# HHV_SCA_Demo-P1.net
KiCad netlist of a schematic drawn in EAGLE
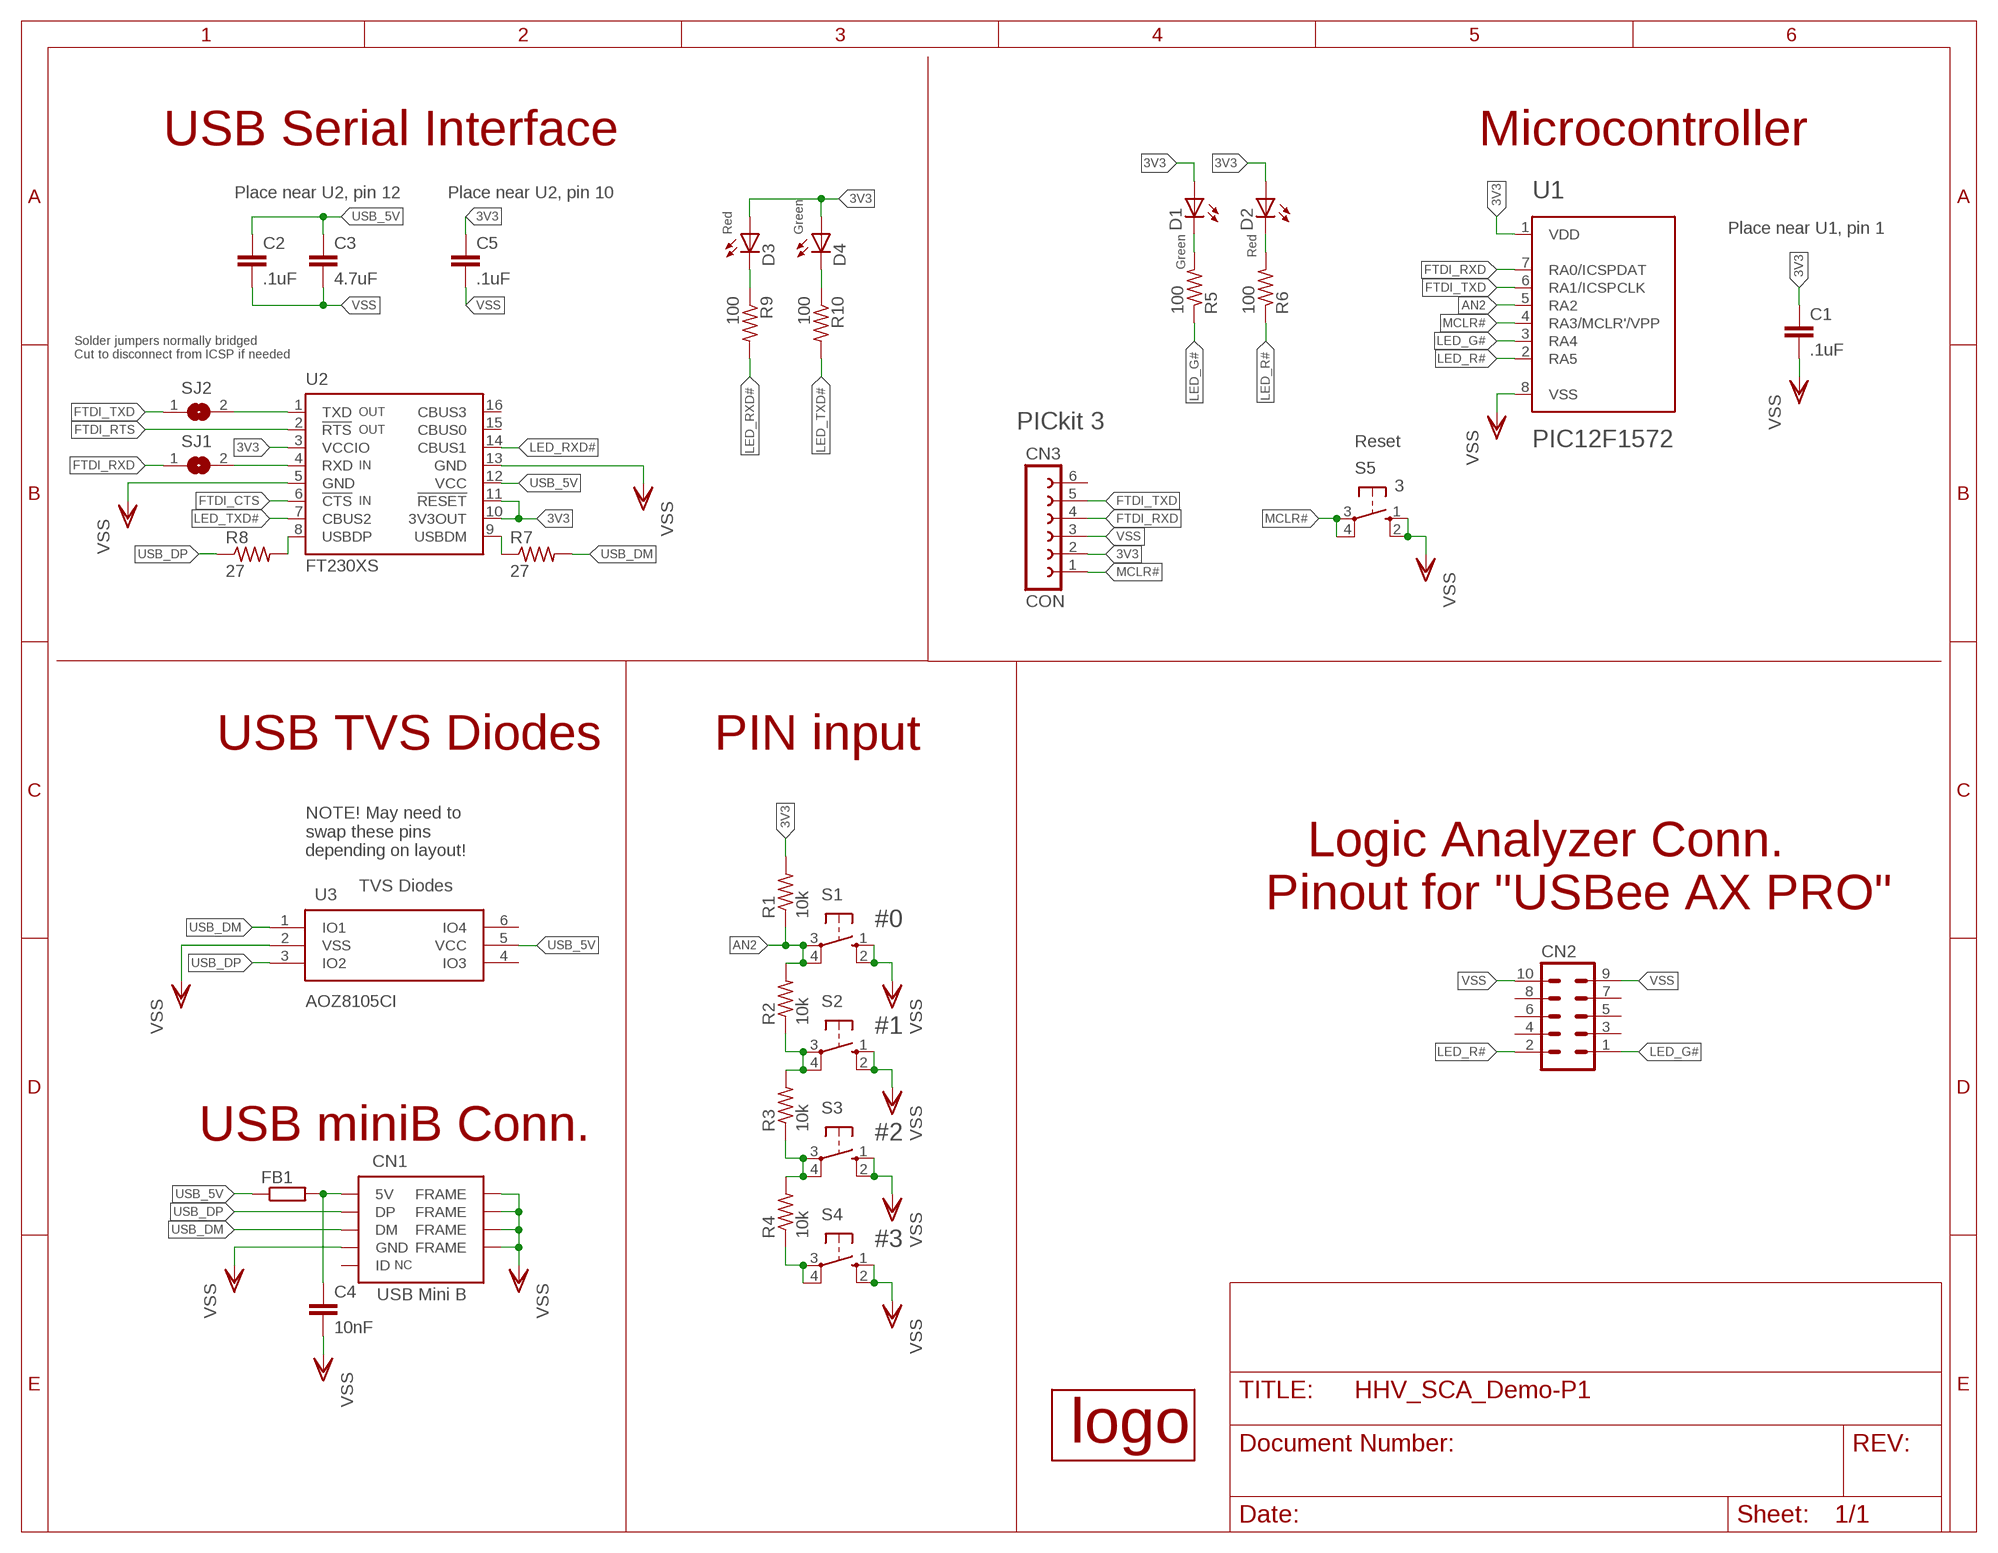
[diagram p0: schematic, sheet 1]

(export (version "E")
  (design (tool "Eeschema 10.0.6"))
  (components
    (comp (ref "C1")
      (value ".1uF")
      (footprint "eagle-import:C0603K")
      (libsource (lib "eagle-import") (part "C-EUC0603K"))
    )
    (comp (ref "C2")
      (value ".1uF")
      (footprint "eagle-import:C0603K")
      (libsource (lib "eagle-import") (part "C-EUC0603K"))
    )
    (comp (ref "C3")
      (value "4.7uF")
      (footprint "eagle-import:C0603K")
      (libsource (lib "eagle-import") (part "C-EUC0603K"))
    )
    (comp (ref "C4")
      (value "10nF")
      (footprint "eagle-import:C0603K")
      (libsource (lib "eagle-import") (part "C-EUC0603K"))
    )
    (comp (ref "C5")
      (value ".1uF")
      (footprint "eagle-import:C0603K")
      (libsource (lib "eagle-import") (part "C-EUC0603K"))
    )
    (comp (ref "CN1")
      (value "MINIUSB-SMD")
      (footprint "eagle-import:MINIUSB-SMD")
      (libsource (lib "eagle-import") (part "MINIUSB-SMD"))
    )
    (comp (ref "CN2")
      (value "MA05-2")
      (footprint "eagle-import:MA05-2")
      (libsource (lib "eagle-import") (part "MA05-2"))
    )
    (comp (ref "CN3")
      (value "CON")
      (footprint "eagle-import:FE06")
      (libsource (lib "eagle-import") (part "FE06-1"))
    )
    (comp (ref "D1")
      (value "LED3MM")
      (footprint "eagle-import:LED3MM")
      (libsource (lib "eagle-import") (part "LED3MM"))
    )
    (comp (ref "D2")
      (value "LED3MM")
      (footprint "eagle-import:LED3MM")
      (libsource (lib "eagle-import") (part "LED3MM"))
    )
    (comp (ref "D3")
      (value "LED3MM")
      (footprint "eagle-import:LED3MM")
      (libsource (lib "eagle-import") (part "LED3MM"))
    )
    (comp (ref "D4")
      (value "LED3MM")
      (footprint "eagle-import:LED3MM")
      (libsource (lib "eagle-import") (part "LED3MM"))
    )
    (comp (ref "FB1")
      (value "R-EU_R0603")
      (footprint "eagle-import:R0603")
      (libsource (lib "eagle-import") (part "R-EU_R0603"))
    )
    (comp (ref "R1")
      (value "10k")
      (footprint "eagle-import:R0603")
      (libsource (lib "eagle-import") (part "R-US_R0603"))
    )
    (comp (ref "R2")
      (value "10k")
      (footprint "eagle-import:R0603")
      (libsource (lib "eagle-import") (part "R-US_R0603"))
    )
    (comp (ref "R3")
      (value "10k")
      (footprint "eagle-import:R0603")
      (libsource (lib "eagle-import") (part "R-US_R0603"))
    )
    (comp (ref "R4")
      (value "10k")
      (footprint "eagle-import:R0603")
      (libsource (lib "eagle-import") (part "R-US_R0603"))
    )
    (comp (ref "R5")
      (value "100")
      (footprint "eagle-import:R0603")
      (libsource (lib "eagle-import") (part "R-US_R0603"))
    )
    (comp (ref "R6")
      (value "100")
      (footprint "eagle-import:R0603")
      (libsource (lib "eagle-import") (part "R-US_R0603"))
    )
    (comp (ref "R7")
      (value "27")
      (footprint "eagle-import:R0402")
      (libsource (lib "eagle-import") (part "R-US_R0402"))
    )
    (comp (ref "R8")
      (value "27")
      (footprint "eagle-import:R0402")
      (libsource (lib "eagle-import") (part "R-US_R0402"))
    )
    (comp (ref "R9")
      (value "100")
      (footprint "eagle-import:R0603")
      (libsource (lib "eagle-import") (part "R-US_R0603"))
    )
    (comp (ref "R10")
      (value "100")
      (footprint "eagle-import:R0603")
      (libsource (lib "eagle-import") (part "R-US_R0603"))
    )
    (comp (ref "S1")
      (value "10-XX")
      (footprint "eagle-import:B3F-10XX")
      (fields (field (name "MPN") "B3F-1000"))
      (libsource (lib "eagle-import") (part "10-XX"))
    )
    (comp (ref "S2")
      (value "10-XX")
      (footprint "eagle-import:B3F-10XX")
      (fields (field (name "MPN") "B3F-1000"))
      (libsource (lib "eagle-import") (part "10-XX"))
    )
    (comp (ref "S3")
      (value "10-XX")
      (footprint "eagle-import:B3F-10XX")
      (fields (field (name "MPN") "B3F-1000"))
      (libsource (lib "eagle-import") (part "10-XX"))
    )
    (comp (ref "S4")
      (value "10-XX")
      (footprint "eagle-import:B3F-10XX")
      (fields (field (name "MPN") "B3F-1000"))
      (libsource (lib "eagle-import") (part "10-XX"))
    )
    (comp (ref "S5")
      (value "3")
      (footprint "eagle-import:B3F-10XX")
      (fields (field (name "MPN") "B3F-1000"))
      (libsource (lib "eagle-import") (part "10-XX"))
    )
    (comp (ref "SJ1") (value "SJ") (footprint "eagle-import:SJ") (libsource (lib "eagle-import") (part "SJ")))
    (comp (ref "SJ2") (value "SJ") (footprint "eagle-import:SJ") (libsource (lib "eagle-import") (part "SJ")))
    (comp (ref "U$1")
      (value "KBELOGO-SILK")
      (footprint "eagle-import:KBELOGO-SILK")
      (libsource (lib "eagle-import") (part "KBELOGO-SILK"))
    )
    (comp (ref "U1")
      (value "PIC12F1572")
      (footprint "eagle-import:DIL8")
      (libsource (lib "eagle-import") (part "PIC12F1571"))
    )
    (comp (ref "U2")
      (value "FT230XS")
      (footprint "eagle-import:SSOP16")
      (libsource (lib "eagle-import") (part "FT230XS"))
    )
    (comp (ref "U3")
      (value "AOZ8105CI")
      (footprint "eagle-import:SOT23-6L")
      (libsource (lib "eagle-import") (part "AOZ8105CI"))
    )
  )
  (nets
    (net (code "1") (name "3V3") (class "Default")
      (node (ref "C1") (pin "1") (pinfunction "1_1") (pintype "passive"))
      (node (ref "C5") (pin "1") (pinfunction "1_1") (pintype "passive"))
      (node (ref "CN3") (pin "2") (pinfunction "2_2") (pintype "passive"))
      (node (ref "D1") (pin "A") (pinfunction "A_A") (pintype "passive"))
      (node (ref "D2") (pin "A") (pinfunction "A_A") (pintype "passive"))
      (node (ref "D3") (pin "A") (pinfunction "A_A") (pintype "passive"))
      (node (ref "D4") (pin "A") (pinfunction "A_A") (pintype "passive"))
      (node (ref "R1") (pin "2") (pinfunction "2_2") (pintype "passive"))
      (node (ref "U1") (pin "1") (pinfunction "VDD_1") (pintype "power_in"))
      (node (ref "U2") (pin "10") (pinfunction "3V3OUT_10") (pintype "output"))
      (node (ref "U2") (pin "11") (pinfunction "~{RESET}_11") (pintype "input"))
      (node (ref "U2") (pin "3") (pinfunction "VCCIO_3") (pintype "power_in"))
    )
    (net (code "2") (name "AN2") (class "Default")
      (node (ref "R1") (pin "1") (pinfunction "1_1") (pintype "passive"))
      (node (ref "R2") (pin "2") (pinfunction "2_2") (pintype "passive"))
      (node (ref "S1") (pin "3") (pinfunction "P_3") (pintype "passive"))
      (node (ref "S1") (pin "4") (pinfunction "P1_4") (pintype "passive"))
      (node (ref "U1") (pin "5") (pinfunction "RA2_5") (pintype "bidirectional"))
    )
    (net (code "3") (name "FTDI_CTS") (class "Default")
      (node (ref "U2") (pin "6") (pinfunction "~{CTS}_6") (pintype "input"))
    )
    (net (code "4") (name "FTDI_RTS") (class "Default")
      (node (ref "U2") (pin "2") (pinfunction "~{RTS}_2") (pintype "output"))
    )
    (net (code "5") (name "FTDI_RXD") (class "Default")
      (node (ref "CN3") (pin "4") (pinfunction "4_4") (pintype "passive"))
      (node (ref "SJ1") (pin "1") (pinfunction "1_1") (pintype "passive"))
      (node (ref "U1") (pin "7") (pinfunction "RA0/ICSPDAT_7") (pintype "bidirectional"))
    )
    (net (code "6") (name "FTDI_TXD") (class "Default")
      (node (ref "CN3") (pin "5") (pinfunction "5_5") (pintype "passive"))
      (node (ref "SJ2") (pin "1") (pinfunction "1_1") (pintype "passive"))
      (node (ref "U1") (pin "6") (pinfunction "RA1/ICSPCLK_6") (pintype "bidirectional"))
    )
    (net (code "7") (name "LED_G#") (class "Default")
      (node (ref "CN2") (pin "1") (pinfunction "1_1") (pintype "passive"))
      (node (ref "R5") (pin "1") (pinfunction "1_1") (pintype "passive"))
      (node (ref "U1") (pin "3") (pinfunction "RA4_3") (pintype "bidirectional"))
    )
    (net (code "8") (name "LED_R#") (class "Default")
      (node (ref "CN2") (pin "2") (pinfunction "2_2") (pintype "passive"))
      (node (ref "R6") (pin "1") (pinfunction "1_1") (pintype "passive"))
      (node (ref "U1") (pin "2") (pinfunction "RA5_2") (pintype "bidirectional"))
    )
    (net (code "9") (name "LED_RXD#") (class "Default")
      (node (ref "R9") (pin "2") (pinfunction "2_2") (pintype "passive"))
      (node (ref "U2") (pin "14") (pinfunction "CBUS1_14") (pintype "bidirectional"))
    )
    (net (code "10") (name "LED_TXD#") (class "Default")
      (node (ref "R10") (pin "2") (pinfunction "2_2") (pintype "passive"))
      (node (ref "U2") (pin "7") (pinfunction "CBUS2_7") (pintype "bidirectional"))
    )
    (net (code "11") (name "MCLR#") (class "Default")
      (node (ref "CN3") (pin "1") (pinfunction "1_1") (pintype "passive"))
      (node (ref "S5") (pin "3") (pinfunction "P_3") (pintype "passive"))
      (node (ref "S5") (pin "4") (pinfunction "P1_4") (pintype "passive"))
      (node (ref "U1") (pin "4") (pinfunction "RA3/MCLR'/VPP_4") (pintype "bidirectional"))
    )
    (net (code "12") (name "Net-(C4-Pad1)") (class "Default")
      (node (ref "C4") (pin "1") (pinfunction "1_1") (pintype "passive"))
      (node (ref "CN1") (pin "5V") (pinfunction "5V_5V") (pintype "bidirectional"))
      (node (ref "FB1") (pin "2") (pinfunction "2_2") (pintype "passive"))
    )
    (net (code "13") (name "Net-(D1-C)") (class "Default")
      (node (ref "D1") (pin "K") (pinfunction "C_K") (pintype "passive"))
      (node (ref "R5") (pin "2") (pinfunction "2_2") (pintype "passive"))
    )
    (net (code "14") (name "Net-(D2-C)") (class "Default")
      (node (ref "D2") (pin "K") (pinfunction "C_K") (pintype "passive"))
      (node (ref "R6") (pin "2") (pinfunction "2_2") (pintype "passive"))
    )
    (net (code "15") (name "Net-(D3-C)") (class "Default")
      (node (ref "D3") (pin "K") (pinfunction "C_K") (pintype "passive"))
      (node (ref "R9") (pin "1") (pinfunction "1_1") (pintype "passive"))
    )
    (net (code "16") (name "Net-(D4-C)") (class "Default")
      (node (ref "D4") (pin "K") (pinfunction "C_K") (pintype "passive"))
      (node (ref "R10") (pin "1") (pinfunction "1_1") (pintype "passive"))
    )
    (net (code "17") (name "Net-(S2-P)") (class "Default")
      (node (ref "R2") (pin "1") (pinfunction "1_1") (pintype "passive"))
      (node (ref "R3") (pin "2") (pinfunction "2_2") (pintype "passive"))
      (node (ref "S2") (pin "3") (pinfunction "P_3") (pintype "passive"))
      (node (ref "S2") (pin "4") (pinfunction "P1_4") (pintype "passive"))
    )
    (net (code "18") (name "Net-(S3-P)") (class "Default")
      (node (ref "R3") (pin "1") (pinfunction "1_1") (pintype "passive"))
      (node (ref "R4") (pin "2") (pinfunction "2_2") (pintype "passive"))
      (node (ref "S3") (pin "3") (pinfunction "P_3") (pintype "passive"))
      (node (ref "S3") (pin "4") (pinfunction "P1_4") (pintype "passive"))
    )
    (net (code "19") (name "Net-(S4-P)") (class "Default")
      (node (ref "R4") (pin "1") (pinfunction "1_1") (pintype "passive"))
      (node (ref "S4") (pin "3") (pinfunction "P_3") (pintype "passive"))
      (node (ref "S4") (pin "4") (pinfunction "P1_4") (pintype "passive"))
    )
    (net (code "20") (name "Net-(U2-RXD)") (class "Default")
      (node (ref "SJ1") (pin "2") (pinfunction "2_2") (pintype "passive"))
      (node (ref "U2") (pin "4") (pinfunction "RXD_4") (pintype "input"))
    )
    (net (code "21") (name "Net-(U2-TXD)") (class "Default")
      (node (ref "SJ2") (pin "2") (pinfunction "2_2") (pintype "passive"))
      (node (ref "U2") (pin "1") (pinfunction "TXD_1") (pintype "output"))
    )
    (net (code "22") (name "Net-(U2-USBDM)") (class "Default")
      (node (ref "R7") (pin "1") (pinfunction "1_1") (pintype "passive"))
      (node (ref "U2") (pin "9") (pinfunction "USBDM_9") (pintype "input"))
    )
    (net (code "23") (name "Net-(U2-USBDP)") (class "Default")
      (node (ref "R8") (pin "2") (pinfunction "2_2") (pintype "passive"))
      (node (ref "U2") (pin "8") (pinfunction "USBDP_8") (pintype "input"))
    )
    (net (code "24") (name "USB_5V") (class "Default")
      (node (ref "C2") (pin "1") (pinfunction "1_1") (pintype "passive"))
      (node (ref "C3") (pin "1") (pinfunction "1_1") (pintype "passive"))
      (node (ref "FB1") (pin "1") (pinfunction "1_1") (pintype "passive"))
      (node (ref "U2") (pin "12") (pinfunction "VCC_12") (pintype "power_in"))
      (node (ref "U3") (pin "5") (pinfunction "VCC_5") (pintype "bidirectional"))
    )
    (net (code "25") (name "USB_DM") (class "Default")
      (node (ref "CN1") (pin "USB_DM") (pinfunction "DM_USB_DM") (pintype "bidirectional"))
      (node (ref "R7") (pin "2") (pinfunction "2_2") (pintype "passive"))
      (node (ref "U3") (pin "1") (pinfunction "IO1_1") (pintype "bidirectional"))
    )
    (net (code "26") (name "USB_DP") (class "Default")
      (node (ref "CN1") (pin "USB_DP") (pinfunction "DP_USB_DP") (pintype "bidirectional"))
      (node (ref "R8") (pin "1") (pinfunction "1_1") (pintype "passive"))
      (node (ref "U3") (pin "3") (pinfunction "IO2_3") (pintype "bidirectional"))
    )
    (net (code "27") (name "VSS") (class "Default")
      (node (ref "C1") (pin "2") (pinfunction "2_2") (pintype "passive"))
      (node (ref "C2") (pin "2") (pinfunction "2_2") (pintype "passive"))
      (node (ref "C3") (pin "2") (pinfunction "2_2") (pintype "passive"))
      (node (ref "C4") (pin "2") (pinfunction "2_2") (pintype "passive"))
      (node (ref "C5") (pin "2") (pinfunction "2_2") (pintype "passive"))
      (node (ref "CN1") (pin "GND@0") (pinfunction "FRAME_GND@0") (pintype "bidirectional"))
      (node (ref "CN1") (pin "GND@1") (pinfunction "FRAME_GND@1") (pintype "bidirectional"))
      (node (ref "CN1") (pin "GND@2") (pinfunction "FRAME_GND@2") (pintype "bidirectional"))
      (node (ref "CN1") (pin "GND@3") (pinfunction "FRAME_GND@3") (pintype "bidirectional"))
      (node (ref "CN1") (pin "VSS") (pinfunction "GND_VSS") (pintype "bidirectional"))
      (node (ref "CN2") (pin "10") (pinfunction "10_10") (pintype "passive"))
      (node (ref "CN2") (pin "9") (pinfunction "9_9") (pintype "passive"))
      (node (ref "CN3") (pin "3") (pinfunction "3_3") (pintype "passive"))
      (node (ref "S1") (pin "1") (pinfunction "S_1") (pintype "passive"))
      (node (ref "S1") (pin "2") (pinfunction "S1_2") (pintype "passive"))
      (node (ref "S2") (pin "1") (pinfunction "S_1") (pintype "passive"))
      (node (ref "S2") (pin "2") (pinfunction "S1_2") (pintype "passive"))
      (node (ref "S3") (pin "1") (pinfunction "S_1") (pintype "passive"))
      (node (ref "S3") (pin "2") (pinfunction "S1_2") (pintype "passive"))
      (node (ref "S4") (pin "1") (pinfunction "S_1") (pintype "passive"))
      (node (ref "S4") (pin "2") (pinfunction "S1_2") (pintype "passive"))
      (node (ref "S5") (pin "1") (pinfunction "S_1") (pintype "passive"))
      (node (ref "S5") (pin "2") (pinfunction "S1_2") (pintype "passive"))
      (node (ref "U1") (pin "8") (pinfunction "VSS_8") (pintype "power_in"))
      (node (ref "U2") (pin "13") (pinfunction "GND_13") (pintype "power_in"))
      (node (ref "U2") (pin "5") (pinfunction "GND_5") (pintype "power_in"))
      (node (ref "U3") (pin "2") (pinfunction "VSS_2") (pintype "bidirectional"))
    )
    (net (code "28") (name "unconnected-(CN1-PadID)") (class "Default")
      (node (ref "CN1") (pin "ID") (pinfunction "ID_ID") (pintype "bidirectional"))
    )
    (net (code "29") (name "unconnected-(CN2-Pad3)") (class "Default")
      (node (ref "CN2") (pin "3") (pinfunction "3_3") (pintype "passive"))
    )
    (net (code "30") (name "unconnected-(CN2-Pad4)") (class "Default")
      (node (ref "CN2") (pin "4") (pinfunction "4_4") (pintype "passive"))
    )
    (net (code "31") (name "unconnected-(CN2-Pad5)") (class "Default")
      (node (ref "CN2") (pin "5") (pinfunction "5_5") (pintype "passive"))
    )
    (net (code "32") (name "unconnected-(CN2-Pad6)") (class "Default")
      (node (ref "CN2") (pin "6") (pinfunction "6_6") (pintype "passive"))
    )
    (net (code "33") (name "unconnected-(CN2-Pad7)") (class "Default")
      (node (ref "CN2") (pin "7") (pinfunction "7_7") (pintype "passive"))
    )
    (net (code "34") (name "unconnected-(CN2-Pad8)") (class "Default")
      (node (ref "CN2") (pin "8") (pinfunction "8_8") (pintype "passive"))
    )
    (net (code "35") (name "unconnected-(CN3-Pad6)") (class "Default")
      (node (ref "CN3") (pin "6") (pinfunction "6_6") (pintype "passive"))
    )
    (net (code "36") (name "unconnected-(U2-CBUS0-Pad15)") (class "Default")
      (node (ref "U2") (pin "15") (pinfunction "CBUS0_15") (pintype "bidirectional"))
    )
    (net (code "37") (name "unconnected-(U2-CBUS3-Pad16)") (class "Default")
      (node (ref "U2") (pin "16") (pinfunction "CBUS3_16") (pintype "bidirectional"))
    )
    (net (code "38") (name "unconnected-(U3-IO3-Pad4)") (class "Default")
      (node (ref "U3") (pin "4") (pinfunction "IO3_4") (pintype "bidirectional"))
    )
    (net (code "39") (name "unconnected-(U3-IO4-Pad6)") (class "Default")
      (node (ref "U3") (pin "6") (pinfunction "IO4_6") (pintype "bidirectional"))
    )
  )
)
